# Supply.net
KiCad netlist of a schematic drawn in Altium Designer
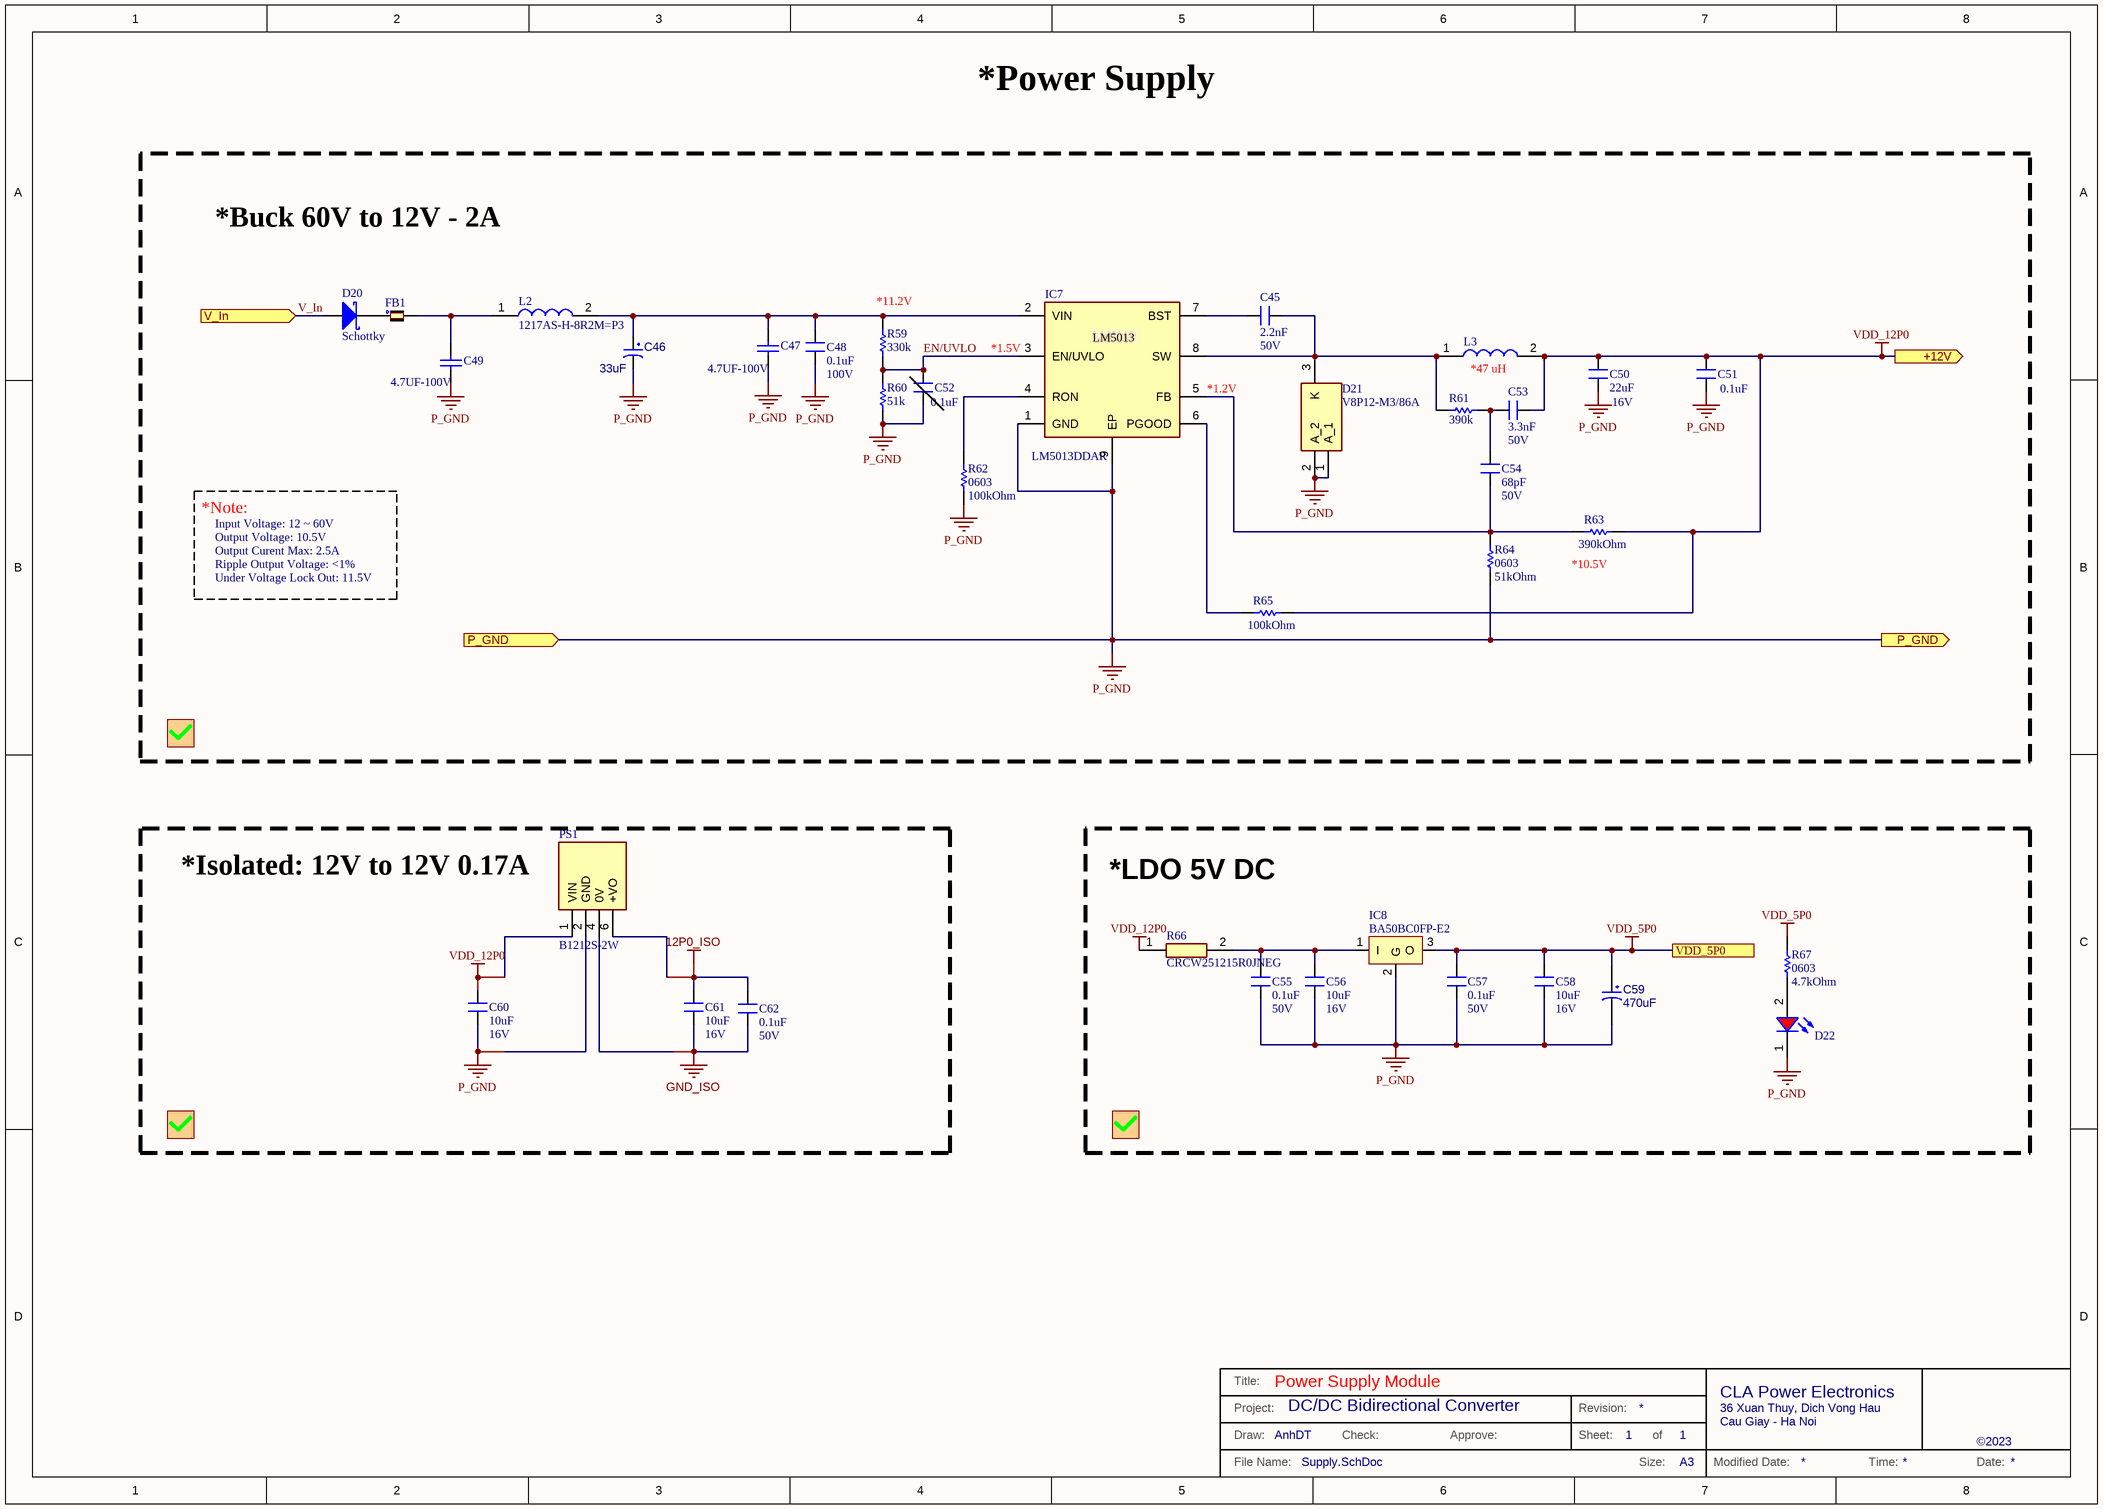
[diagram p0: Supply.SchDoc]

(export (version "E")
  (design (tool "Eeschema 10.0.6"))
  (components
    (comp (ref "C45")
      (value "2.2nF")
      (footprint "C_0603")
      (description "CAP CER 2.2nF 50V X7R 0805")
      (fields
        (field (name "MANUFACTURER") "Samsung Electro-Mechanics")
        (field (name "PART NUMBER") "C0805C222J5GEC7800")
        (field (name "ALTIUM_VALUE") "50V")
      )
      (libsource (lib "S1200_Capacitor") (part "Cap_Cer_0805_10pF"))
    )
    (comp (ref "C46")
      (value "33uF")
      (footprint "C_ALU_TH_8p0D11p5")
      (description "CAP ALUM 33UF 20% 80V RADIAL")
      (fields (field (name "MANUFACTURER") "PANASONIC") (field (name "PART NUMBER") "80ZLH33MEFC6.3X11"))
      (libsource (lib "Selex_Component_Lib") (part "Cap_Alu_TH_8P0D3P5_22uF"))
    )
    (comp (ref "C47")
      (value "4.7UF-100V")
      (footprint "C_1210")
      (description "CAP CER 4.7uF 80V X7R 1210")
      (fields
        (field (name "PART NUMBER") "GRM32ER71K475KE14L")
        (field (name "MANUFACTURER") "TDK Corporation")
      )
      (libsource (lib "DC_DC_Power_V3.0") (part "Cap 1210"))
    )
    (comp (ref "C48")
      (value "0.1uF")
      (footprint "C_0805")
      (description "CAP CER 0.1uF 100V X7R 0805")
      (fields (field (name "MANUFACTURER") "Samsung Electro-Mechanics") (field (name "ALTIUM_VALUE") "100V"))
      (libsource (lib "S1200_Capacitor") (part "Cap_Cer_0805_10pF"))
    )
    (comp (ref "C49")
      (value "4.7UF-100V")
      (footprint "C_1210")
      (description "CAP CER 4.7uF 80V X7R 1210")
      (fields
        (field (name "PART NUMBER") "GRM32ER71K475KE14L")
        (field (name "MANUFACTURER") "TDK Corporation")
      )
      (libsource (lib "DC_DC_Power_V3.0") (part "Cap 1210"))
    )
    (comp (ref "C50")
      (value "22uF")
      (footprint "C_1210")
      (description "CAP CER 22uF 16V X7R 1210")
      (fields
        (field (name "MANUFACTURER") "Samsung Electro-Mechanics")
        (field (name "PART NUMBER") "CL32A226KOJNNNE")
        (field (name "ALTIUM_VALUE") "16V")
      )
      (libsource (lib "S1200_Capacitor") (part "Cap_Cer_0805_10pF"))
    )
    (comp (ref "C51")
      (value "0.1uF")
      (footprint "C_0603")
      (description "CAP CER 0.1UF 25V X8R 0603")
      (fields
        (field (name "MANUFACTURER") "Murata Electronics")
        (field (name "PART NUMBER") "GCM188R91E104KA37J")
      )
      (libsource (lib "S1200_Capacitor") (part "Cap_Cer_0603_0.1uF_25V"))
    )
    (comp (ref "C52")
      (value "0.1uF")
      (footprint "C_0603")
      (description "CAP CER 0.1UF 100V X7R 0603")
      (fields
        (field (name "MANUFACTURER") "Murata Electronics")
        (field (name "PART NUMBER") "GRM188R72A104KA35D")
      )
      (libsource (lib "S1200_Capacitor") (part "Cap_Cer_0603_0.1uF_100V"))
    )
    (comp (ref "C53")
      (value "3.3nF")
      (footprint "C_0603")
      (description "CAP CER 0805 3.3NF 50V C0G 1%")
      (fields
        (field (name "MANUFACTURER") "Kemet")
        (field (name "PART NUMBER") "C0805C332F5GECAUTO")
        (field (name "ALTIUM_VALUE") "50V")
      )
      (libsource (lib "S1200_Capacitor") (part "Cap_Cer_0805_10pF"))
    )
    (comp (ref "C54")
      (value "68pF")
      (footprint "C_0603")
      (description "CAP CER 68pF 50V C0G 0603")
      (fields
        (field (name "MANUFACTURER") "Kemet")
        (field (name "PART NUMBER") "CL10C680JB81PNC")
        (field (name "ALTIUM_VALUE") "50V")
      )
      (libsource (lib "S1200_Capacitor") (part "Cap_Cer_0805_10pF"))
    )
    (comp (ref "C55")
      (value "0.1uF")
      (footprint "C_0603")
      (description "CAP CER 0.1uF 50V X7R 0603")
      (fields
        (field (name "MANUFACTURER") "Kemet")
        (field (name "PART NUMBER") "CL10C680JB81PNC")
        (field (name "ALTIUM_VALUE") "50V")
      )
      (libsource (lib "S1200_Capacitor") (part "Cap_Cer_0805_10pF"))
    )
    (comp (ref "C56")
      (value "10uF")
      (footprint "C_0805")
      (description "CAP CER 10uF 16V X7R 0805")
      (fields
        (field (name "MANUFACTURER") "Kemet")
        (field (name "PART NUMBER") "CL21A106KOCLRNC")
        (field (name "ALTIUM_VALUE") "16V")
      )
      (libsource (lib "S1200_Capacitor") (part "Cap_Cer_0805_10pF"))
    )
    (comp (ref "C57")
      (value "0.1uF")
      (footprint "C_0603")
      (description "CAP CER 0.1uF 50V X7R 0603")
      (fields
        (field (name "MANUFACTURER") "Kemet")
        (field (name "PART NUMBER") "CL10C680JB81PNC")
        (field (name "ALTIUM_VALUE") "50V")
      )
      (libsource (lib "S1200_Capacitor") (part "Cap_Cer_0805_10pF"))
    )
    (comp (ref "C58")
      (value "10uF")
      (footprint "C_0805")
      (description "CAP CER 10uF 16V X7R 0805")
      (fields
        (field (name "MANUFACTURER") "Kemet")
        (field (name "PART NUMBER") "CL21A106KOCLRNC")
        (field (name "ALTIUM_VALUE") "16V")
      )
      (libsource (lib "S1200_Capacitor") (part "Cap_Cer_0805_10pF"))
    )
    (comp (ref "C59")
      (value "470uF")
      (footprint "C_ALU_TH_8p0D11p5")
      (description "CAP ALUM 470UF 20% 25V RADIAL")
      (fields (field (name "MANUFACTURER") "Rubycon") (field (name "PART NUMBER") "16YXJ220MT16.3X11"))
      (libsource (lib "Selex_Component_Lib") (part "Cap_Alu_TH_8P0D3P5"))
    )
    (comp (ref "C60")
      (value "10uF")
      (footprint "C_0805")
      (description "CAP CER 2.2uF 50V X7R 0805")
      (fields
        (field (name "MANUFACTURER") "Samsung Electro-Mechanics")
        (field (name "PART NUMBER") "CL31B225KBHNNNE")
        (field (name "ALTIUM_VALUE") "16V")
      )
      (libsource (lib "S1200_Capacitor") (part "Cap_Cer_0805_10pF"))
    )
    (comp (ref "C61")
      (value "10uF")
      (footprint "C_0805")
      (description "CAP CER 4.7uF 50V X7R 0805")
      (fields
        (field (name "MANUFACTURER") "Samsung Electro-Mechanics")
        (field (name "PART NUMBER") "CL31B225KBHNNNE")
        (field (name "ALTIUM_VALUE") "16V")
      )
      (libsource (lib "S1200_Capacitor") (part "Cap_Cer_0805_10pF"))
    )
    (comp (ref "C62")
      (value "0.1uF")
      (footprint "C_0603")
      (description "CAP CER 0.1uF 50V X7R 0603")
      (fields
        (field (name "MANUFACTURER") "Kemet")
        (field (name "PART NUMBER") "CL10C680JB81PNC")
        (field (name "ALTIUM_VALUE") "50V")
      )
      (libsource (lib "S1200_Capacitor") (part "Cap_Cer_0805_10pF"))
    )
    (comp (ref "D20")
      (value "Schottky")
      (footprint "DIODE_Schottky_DO214")
      (description "DIODE SCHOTTKY 100V 3A SMA")
      (fields (field (name "MANUFACTURER") "SMC Diode Solutions") (field (name "PART NUMBER") "SS310"))
      (libsource (lib "S1500_Diode") (part "SS34"))
    )
    (comp (ref "D21")
      (value "V8P12-M3/86A")
      (footprint "V8P12M386A")
      (description "DIODE SCHOTTKY 120V 8A TO277A")
      (fields (field (name "MOUSER PART NUMBER") "78-V8P12-M3/86A"))
      (libsource (lib "*") (part "V8P12-M3_86A"))
    )
    (comp (ref "D22")
      (value "LED-SMD")
      (footprint "SM-LED-0805-Green")
      (description "LED GREEN DIFFUSED 0805 SMD")
      (fields (field (name "MANUFACTURER") "OSRAM Opto Semiconductors Inc."))
      (libsource (lib "Motor Control SELEX MOTORS JSC") (part "LED-SMD"))
    )
    (comp (ref "FB1")
      (value "FerriteBead_1206_270Ohm")
      (footprint "FERRITEBEAD_1206")
      (description "FERRITE BEAD 270 OHM 1206 1LN")
      (fields
        (field (name "MANUFACTURER") "Murata Electronics")
        (field (name "PART NUMBER") "BLM31KN271SH1L")
      )
      (libsource (lib "S1100_Resistor_FerriteBead") (part "FerriteBead_1206_270Ohm"))
    )
    (comp (ref "IC7")
      (value "LM5013DDAR")
      (footprint "SOIC127P600X170-9N")
      (description "IC REG BUCK ADJ 3.5A 8SO PWR")
      (libsource (lib "Tienanh") (part "LM5012DDAR"))
    )
    (comp (ref "IC8")
      (value "BA50BC0FP-E2")
      (footprint "TO252-123")
      (description "IC REG LINEAR 5V 1A TO252-2")
      (libsource (lib "Motor Control SELEX MOTORS JSC") (part "BA50BC0FP-E2"))
    )
    (comp (ref "L2")
      (value "1217AS-H-8R2M=P3")
      (footprint "1217ASH100MP3")
      (description "Inductor 8.2 uH")
      (fields (field (name "MOUSER PART NUMBER") "81-1217AS-H-8R2MP3"))
      (libsource (lib "*") (part "1217AS-H-8R2M=P3"))
    )
    (comp (ref "L3")
      (value "~")
      (footprint "SRR1260A470M")
      (description "FIXED IND 47UH 2.5A 100 MOHM SMD")
      (fields (field (name "MANUFACTURER") "Taiyo Yuden") (field (name "PART NUMBER") "CDRH127-470"))
      (libsource (lib "Motor Control SELEX MOTORS JSC") (part "Inductor"))
    )
    (comp (ref "PS1")
      (value "B1212S-2W")
      (footprint "SamacSys:B1212S2W")
      (description "Power Supply")
      (libsource (lib "*") (part "B1212S-2W"))
    )
    (comp (ref "R59")
      (value "330k")
      (footprint "R_0603")
      (description "RES 200K OHM 1% 1/10W 0603")
      (fields (field (name "MANUFACTURER") "YAGEO") (field (name "PART NUMBER") "RC0603FR-13200KL"))
      (libsource (lib "S1100_Resistor_FerriteBead") (part "Resistor_0603_10Ohm 1%"))
    )
    (comp (ref "R60")
      (value "51k")
      (footprint "R_0603")
      (description "RES 24k OHM 1% 1/8W 0603")
      (fields (field (name "MANUFACTURER") "YAGEO") (field (name "PART NUMBER") "RC0603FR-1024KL"))
      (libsource (lib "S1100_Resistor_FerriteBead") (part "Resistor_0603_10Ohm 1%"))
    )
    (comp (ref "R61")
      (value "390k")
      (footprint "R_0603")
      (description "RES 390k OHM 1% 1/8W 0603")
      (fields (field (name "MANUFACTURER") "YAGEO") (field (name "PART NUMBER") "RC0603FR-07390KL"))
      (libsource (lib "S1100_Resistor_FerriteBead") (part "Resistor_0603_10Ohm 1%"))
    )
    (comp (ref "R62")
      (value "0603")
      (footprint "R_0603")
      (description "RES SMD 100K OHM 1% 1/8W 0603")
      (fields
        (field (name "MANUFACTURER") "Vishay Beyschlag/Draloric/BC Components")
        (field (name "PART NUMBER") "MCT06030C1003FP500")
        (field (name "ALTIUM_VALUE") "100kOhm")
      )
      (libsource (lib "S1100_Resistor_FerriteBead") (part "Resistor_0603_100kOhm"))
    )
    (comp (ref "R63")
      (value "390kOhm")
      (footprint "R_0603")
      (description "RES SMD 470K OHM 1% 1/10W 0603")
      (fields (field (name "MANUFACTURER") "Walsin Technology Corporation") (field (name "POWER") "1/10W"))
      (libsource (lib "S1100_Resistor_FerriteBead") (part "Resistor_0603_470kOhm"))
    )
    (comp (ref "R64")
      (value "0603")
      (footprint "R_0603")
      (description "RES SMD 51K OHM 1% 1/8W 0603")
      (fields
        (field (name "MANUFACTURER") "YAGEO")
        (field (name "PART NUMBER") "RC0603FR-0751KL")
        (field (name "ALTIUM_VALUE") "51kOhm")
      )
      (libsource (lib "S1100_Resistor_FerriteBead") (part "Resistor_0603_51kOhm"))
    )
    (comp (ref "R65")
      (value "100kOhm")
      (footprint "R_0603")
      (description "RES SMD 100K OHM 1% 1/8W 0603")
      (fields
        (field (name "MANUFACTURER") "Vishay Beyschlag/Draloric/BC Components")
        (field (name "PART NUMBER") "MCT06030C1003FP500")
      )
      (libsource (lib "S1100_Resistor_FerriteBead") (part "Resistor_0603_100kOhm"))
    )
    (comp (ref "R66")
      (value "CRCW251215R0JNEG")
      (footprint "RESC6332X70N")
      (fields (field (name "MOUSER PART NUMBER") "71-CRCW2512J-15-E3"))
      (libsource (lib "*") (part "CRCW251215R0JNEG"))
    )
    (comp (ref "R67")
      (value "0603")
      (footprint "R_0603")
      (description "RES 2K OHM 1% 1/10W 0603")
      (fields
        (field (name "MANUFACTURER") "YAGEO")
        (field (name "PART NUMBER") "RC0603FR-074K7L")
        (field (name "ALTIUM_VALUE") "4.7kOhm")
      )
      (libsource (lib "S1100_Resistor_FerriteBead") (part "Resistor_0603_4.7kOhm"))
    )
  )
  (nets
    (net (code "1") (name "/EN{slash}UVLO") (class "Default")
      (node (ref "C52") (pin "1") (pinfunction "1_1") (pintype "passive"))
      (node (ref "IC7") (pin "3") (pinfunction "EN/UVLO_3") (pintype "passive"))
      (node (ref "R59") (pin "1") (pinfunction "1_1") (pintype "passive"))
      (node (ref "R60") (pin "2") (pinfunction "2_2") (pintype "passive"))
    )
    (net (code "2") (name "/V_In") (class "Default")
      (node (ref "D20") (pin "1") (pinfunction "A_1") (pintype "passive"))
    )
    (net (code "3") (name "12P0_ISO") (class "Default")
      (node (ref "C61") (pin "2") (pinfunction "2_2") (pintype "passive"))
      (node (ref "C62") (pin "2") (pinfunction "2_2") (pintype "passive"))
      (node (ref "PS1") (pin "6") (pinfunction "+VO_6") (pintype "passive"))
    )
    (net (code "4") (name "GND_ISO") (class "Default")
      (node (ref "C61") (pin "1") (pinfunction "1_1") (pintype "passive"))
      (node (ref "C62") (pin "1") (pinfunction "1_1") (pintype "passive"))
      (node (ref "PS1") (pin "4") (pinfunction "0V_4") (pintype "passive"))
    )
    (net (code "5") (name "Net-(C49-Pad2)") (class "Default")
      (node (ref "C49") (pin "2") (pinfunction "2_2") (pintype "passive"))
      (node (ref "FB1") (pin "2") (pinfunction "2_2") (pintype "passive"))
      (node (ref "L2") (pin "1") (pinfunction "1_1") (pintype "passive"))
    )
    (net (code "6") (name "Net-(C53-Pad1)") (class "Default")
      (node (ref "C53") (pin "1") (pinfunction "1_1") (pintype "passive"))
      (node (ref "C54") (pin "2") (pinfunction "2_2") (pintype "passive"))
      (node (ref "R61") (pin "1") (pinfunction "1_1") (pintype "passive"))
    )
    (net (code "7") (name "Net-(D20-K)") (class "Default")
      (node (ref "D20") (pin "2") (pinfunction "K_2") (pintype "passive"))
      (node (ref "FB1") (pin "1") (pinfunction "1_1") (pintype "passive"))
    )
    (net (code "8") (name "Net-(D21-K)") (class "Default")
      (node (ref "C45") (pin "1") (pinfunction "1_1") (pintype "passive"))
      (node (ref "D21") (pin "3") (pinfunction "K_3") (pintype "passive"))
      (node (ref "IC7") (pin "8") (pinfunction "SW_8") (pintype "passive"))
      (node (ref "L3") (pin "1") (pinfunction "1_1") (pintype "passive"))
      (node (ref "R61") (pin "2") (pinfunction "2_2") (pintype "passive"))
    )
    (net (code "9") (name "Net-(D22-A)") (class "Default")
      (node (ref "D22") (pin "2") (pinfunction "A_2") (pintype "passive"))
      (node (ref "R67") (pin "1") (pinfunction "1_1") (pintype "passive"))
    )
    (net (code "10") (name "Net-(IC7-BST)") (class "Default")
      (node (ref "C45") (pin "2") (pinfunction "2_2") (pintype "passive"))
      (node (ref "IC7") (pin "7") (pinfunction "BST_7") (pintype "passive"))
    )
    (net (code "11") (name "Net-(IC7-FB)") (class "Default")
      (node (ref "C54") (pin "1") (pinfunction "1_1") (pintype "passive"))
      (node (ref "IC7") (pin "5") (pinfunction "FB_5") (pintype "passive"))
      (node (ref "R63") (pin "1") (pinfunction "1_1") (pintype "passive"))
      (node (ref "R64") (pin "2") (pinfunction "2_2") (pintype "passive"))
    )
    (net (code "12") (name "Net-(IC7-PGOOD)") (class "Default")
      (node (ref "IC7") (pin "6") (pinfunction "PGOOD_6") (pintype "passive"))
      (node (ref "R65") (pin "2") (pinfunction "2_2") (pintype "passive"))
    )
    (net (code "13") (name "Net-(IC7-RON)") (class "Default")
      (node (ref "IC7") (pin "4") (pinfunction "RON_4") (pintype "passive"))
      (node (ref "R62") (pin "2") (pinfunction "2_2") (pintype "passive"))
    )
    (net (code "14") (name "Net-(IC7-VIN)") (class "Default")
      (node (ref "C46") (pin "1") (pinfunction "1_1") (pintype "passive"))
      (node (ref "C47") (pin "2") (pinfunction "2_2") (pintype "passive"))
      (node (ref "C48") (pin "2") (pinfunction "2_2") (pintype "passive"))
      (node (ref "IC7") (pin "2") (pinfunction "VIN_2") (pintype "passive"))
      (node (ref "L2") (pin "2") (pinfunction "2_2") (pintype "passive"))
      (node (ref "R59") (pin "2") (pinfunction "2_2") (pintype "passive"))
    )
    (net (code "15") (name "Net-(IC8-I)") (class "Default")
      (node (ref "C55") (pin "2") (pinfunction "2_2") (pintype "passive"))
      (node (ref "C56") (pin "2") (pinfunction "2_2") (pintype "passive"))
      (node (ref "IC8") (pin "1") (pinfunction "I_1") (pintype "power_in"))
      (node (ref "R66") (pin "2") (pinfunction "2_2") (pintype "passive"))
    )
    (net (code "16") (name "P_GND") (class "Default")
      (node (ref "C46") (pin "2") (pinfunction "2_2") (pintype "passive"))
      (node (ref "C47") (pin "1") (pinfunction "1_1") (pintype "passive"))
      (node (ref "C48") (pin "1") (pinfunction "1_1") (pintype "passive"))
      (node (ref "C49") (pin "1") (pinfunction "1_1") (pintype "passive"))
      (node (ref "C50") (pin "1") (pinfunction "1_1") (pintype "passive"))
      (node (ref "C51") (pin "1") (pinfunction "1_1") (pintype "passive"))
      (node (ref "C52") (pin "2") (pinfunction "2_2") (pintype "passive"))
      (node (ref "C55") (pin "1") (pinfunction "1_1") (pintype "passive"))
      (node (ref "C56") (pin "1") (pinfunction "1_1") (pintype "passive"))
      (node (ref "C57") (pin "1") (pinfunction "1_1") (pintype "passive"))
      (node (ref "C58") (pin "1") (pinfunction "1_1") (pintype "passive"))
      (node (ref "C59") (pin "2") (pinfunction "2_2") (pintype "passive"))
      (node (ref "C60") (pin "1") (pinfunction "1_1") (pintype "passive"))
      (node (ref "D21") (pin "1") (pinfunction "A_1_1") (pintype "passive"))
      (node (ref "D21") (pin "2") (pinfunction "A_2_2") (pintype "passive"))
      (node (ref "D22") (pin "1") (pinfunction "K_1") (pintype "passive"))
      (node (ref "IC7") (pin "1") (pinfunction "GND_1") (pintype "passive"))
      (node (ref "IC7") (pin "9") (pinfunction "EP_9") (pintype "passive"))
      (node (ref "IC8") (pin "2") (pinfunction "G_2") (pintype "power_in"))
      (node (ref "PS1") (pin "2") (pinfunction "GND_2") (pintype "passive"))
      (node (ref "R60") (pin "1") (pinfunction "1_1") (pintype "passive"))
      (node (ref "R62") (pin "1") (pinfunction "1_1") (pintype "passive"))
      (node (ref "R64") (pin "1") (pinfunction "1_1") (pintype "passive"))
    )
    (net (code "17") (name "VDD_5P0") (class "Default")
      (node (ref "C57") (pin "2") (pinfunction "2_2") (pintype "passive"))
      (node (ref "C58") (pin "2") (pinfunction "2_2") (pintype "passive"))
      (node (ref "C59") (pin "1") (pinfunction "1_1") (pintype "passive"))
      (node (ref "IC8") (pin "3") (pinfunction "O_3") (pintype "power_in"))
      (node (ref "R67") (pin "2") (pinfunction "2_2") (pintype "passive"))
    )
    (net (code "18") (name "VDD_12P0") (class "Default")
      (node (ref "C50") (pin "2") (pinfunction "2_2") (pintype "passive"))
      (node (ref "C51") (pin "2") (pinfunction "2_2") (pintype "passive"))
      (node (ref "C53") (pin "2") (pinfunction "2_2") (pintype "passive"))
      (node (ref "C60") (pin "2") (pinfunction "2_2") (pintype "passive"))
      (node (ref "L3") (pin "2") (pinfunction "2_2") (pintype "passive"))
      (node (ref "PS1") (pin "1") (pinfunction "VIN_1") (pintype "passive"))
      (node (ref "R63") (pin "2") (pinfunction "2_2") (pintype "passive"))
      (node (ref "R65") (pin "1") (pinfunction "1_1") (pintype "passive"))
      (node (ref "R66") (pin "1") (pinfunction "1_1") (pintype "passive"))
    )
  )
)
